# motor_driver_v3_0.net
KiCad netlist of a schematic drawn in EAGLE
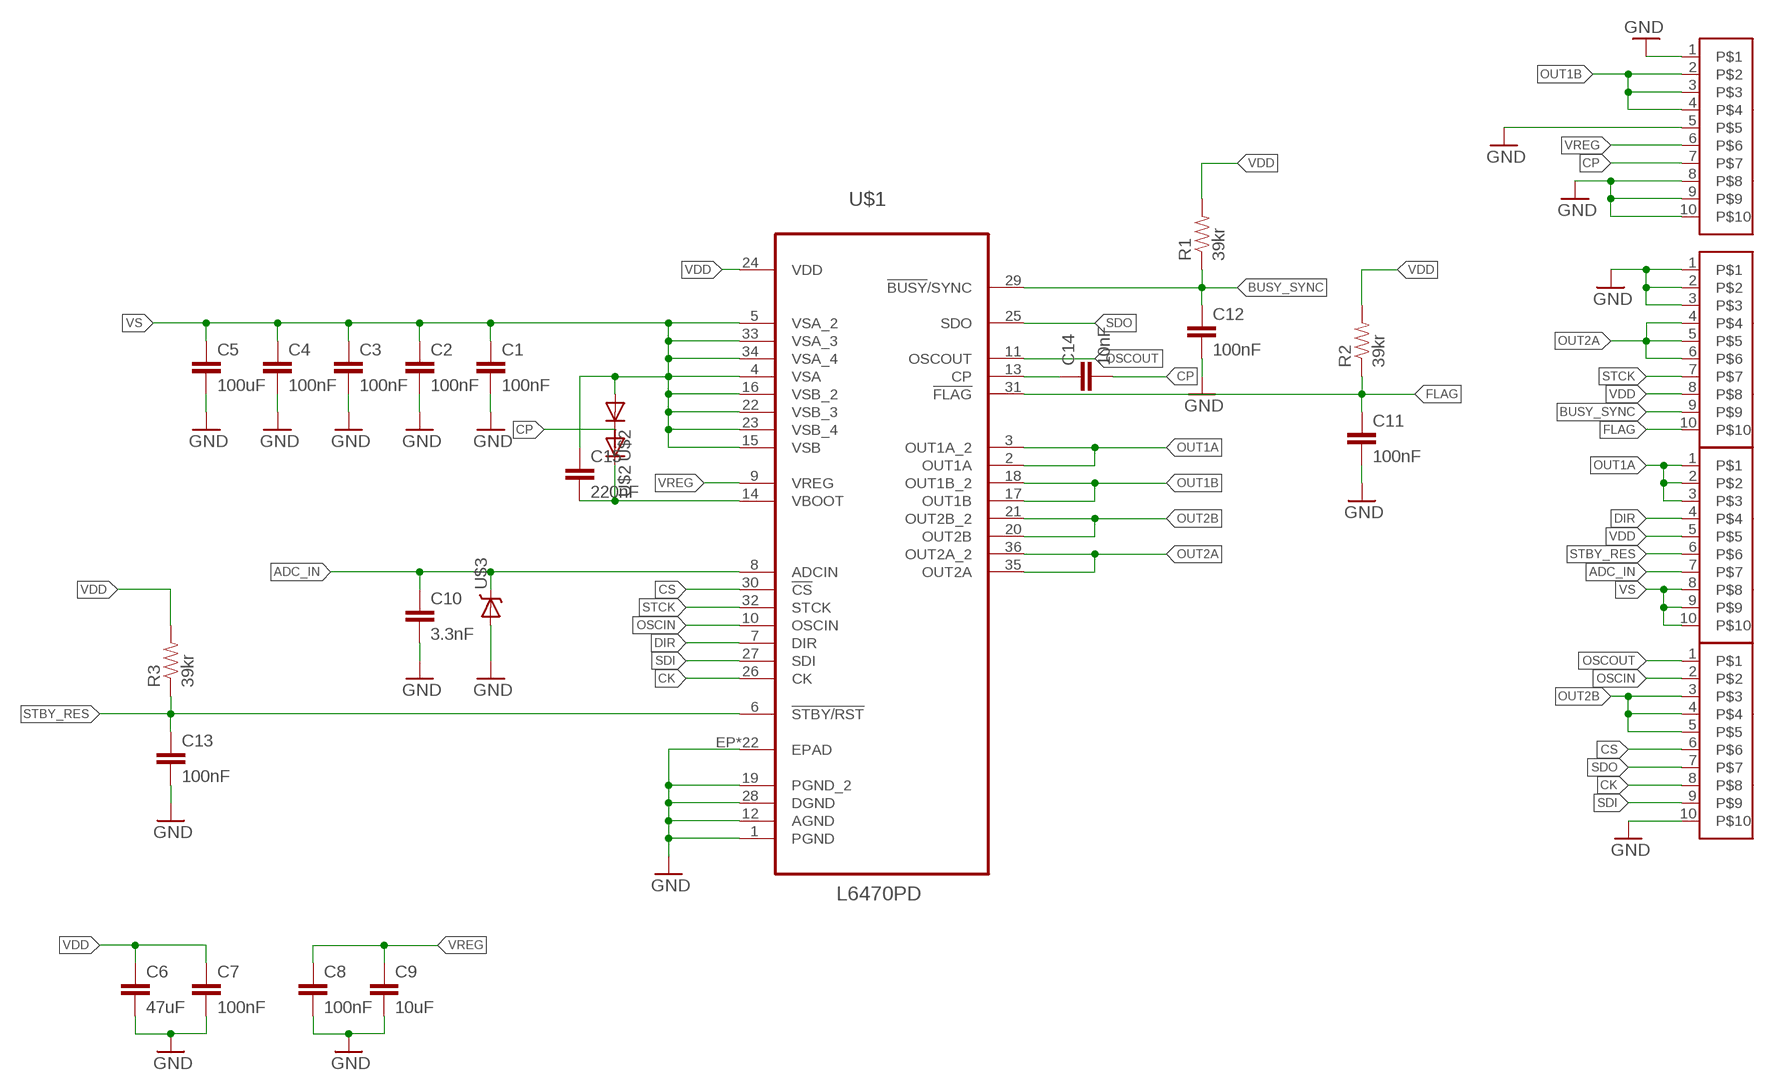
[diagram p0: schematic, sheet 1]

(export (version "E")
  (design (tool "Eeschema 10.0.6"))
  (components
    (comp (ref "C1")
      (value "100nF")
      (footprint "eagle-import:0805-CAP")
      (libsource (lib "eagle-import") (part "CAP0805"))
    )
    (comp (ref "C2")
      (value "100nF")
      (footprint "eagle-import:0805-CAP")
      (libsource (lib "eagle-import") (part "CAP0805"))
    )
    (comp (ref "C3")
      (value "100nF")
      (footprint "eagle-import:0805-CAP")
      (libsource (lib "eagle-import") (part "CAP0805"))
    )
    (comp (ref "C4")
      (value "100nF")
      (footprint "eagle-import:0805-CAP")
      (libsource (lib "eagle-import") (part "CAP0805"))
    )
    (comp (ref "C5")
      (value "100uF")
      (footprint "eagle-import:CAP-10X12")
      (libsource (lib "eagle-import") (part "CAP"))
    )
    (comp (ref "C6")
      (value "47uF")
      (footprint "eagle-import:1206-CAP")
      (libsource (lib "eagle-import") (part "CAP1206"))
    )
    (comp (ref "C7")
      (value "100nF")
      (footprint "eagle-import:0805-CAP")
      (libsource (lib "eagle-import") (part "CAP0805"))
    )
    (comp (ref "C8")
      (value "100nF")
      (footprint "eagle-import:0805-CAP")
      (libsource (lib "eagle-import") (part "CAP0805"))
    )
    (comp (ref "C9")
      (value "10uF")
      (footprint "eagle-import:0805-CAP")
      (libsource (lib "eagle-import") (part "CAP0805"))
    )
    (comp (ref "C10")
      (value "3.3nF")
      (footprint "eagle-import:0805-CAP")
      (libsource (lib "eagle-import") (part "CAP0805"))
    )
    (comp (ref "C11")
      (value "100nF")
      (footprint "eagle-import:0805-CAP")
      (libsource (lib "eagle-import") (part "CAP0805"))
    )
    (comp (ref "C12")
      (value "100nF")
      (footprint "eagle-import:0805-CAP")
      (libsource (lib "eagle-import") (part "CAP0805"))
    )
    (comp (ref "C13")
      (value "100nF")
      (footprint "eagle-import:0805-CAP")
      (libsource (lib "eagle-import") (part "CAP0805"))
    )
    (comp (ref "C14")
      (value "10nF")
      (footprint "eagle-import:0805-CAP")
      (libsource (lib "eagle-import") (part "CAP0805"))
    )
    (comp (ref "C15")
      (value "220nF")
      (footprint "eagle-import:0805-CAP")
      (libsource (lib "eagle-import") (part "CAP0805"))
    )
    (comp (ref "R1")
      (value "39kr")
      (footprint "eagle-import:0805")
      (libsource (lib "eagle-import") (part "RESISTOR"))
    )
    (comp (ref "R2")
      (value "39kr")
      (footprint "eagle-import:0805")
      (libsource (lib "eagle-import") (part "RESISTOR"))
    )
    (comp (ref "R3")
      (value "39kr")
      (footprint "eagle-import:0805")
      (libsource (lib "eagle-import") (part "RESISTOR"))
    )
    (comp (ref "U$1")
      (value "L6470PD")
      (footprint "eagle-import:SOP65P1400X360-37N")
      (libsource (lib "eagle-import") (part "L6470PD"))
    )
    (comp (ref "U$2")
      (value "BAV99")
      (footprint "eagle-import:BAV99")
      (libsource (lib "eagle-import") (part "BAV99"))
    )
    (comp (ref "U$3")
      (value "BZX585")
      (footprint "eagle-import:BZX585")
      (libsource (lib "eagle-import") (part "BZX585"))
    )
    (comp (ref "U$4")
      (value "CON_TH_10PINS")
      (footprint "eagle-import:CON_TH_10POS")
      (libsource (lib "eagle-import") (part "CON_TH_10PINS"))
    )
    (comp (ref "U$5")
      (value "CON_TH_10PINS")
      (footprint "eagle-import:CON_TH_10POS")
      (libsource (lib "eagle-import") (part "CON_TH_10PINS"))
    )
    (comp (ref "U$6")
      (value "CON_TH_10PINS")
      (footprint "eagle-import:CON_TH_10POS")
      (libsource (lib "eagle-import") (part "CON_TH_10PINS"))
    )
    (comp (ref "U$7")
      (value "CON_TH_10PINS")
      (footprint "eagle-import:CON_TH_10POS")
      (libsource (lib "eagle-import") (part "CON_TH_10PINS"))
    )
  )
  (nets
    (net (code "1") (name "ADC_IN") (class "Default")
      (node (ref "C10") (pin "P$1") (pinfunction "1_P$1") (pintype "passive"))
      (node (ref "U$1") (pin "8") (pinfunction "ADCIN_8") (pintype "input"))
      (node (ref "U$3") (pin "P$1") (pinfunction "1_P$1") (pintype "passive"))
      (node (ref "U$4") (pin "7") (pinfunction "P$7_7") (pintype "bidirectional"))
    )
    (net (code "2") (name "BUSY_SYNC") (class "Default")
      (node (ref "C12") (pin "P$1") (pinfunction "1_P$1") (pintype "passive"))
      (node (ref "R1") (pin "1") (pinfunction "1_1") (pintype "passive"))
      (node (ref "U$1") (pin "29") (pinfunction "~{BUSY}/SYNC_29") (pintype "output"))
      (node (ref "U$5") (pin "9") (pinfunction "P$9_9") (pintype "bidirectional"))
    )
    (net (code "3") (name "CK") (class "Default")
      (node (ref "U$1") (pin "26") (pinfunction "CK_26") (pintype "input"))
      (node (ref "U$7") (pin "8") (pinfunction "P$8_8") (pintype "bidirectional"))
    )
    (net (code "4") (name "CP") (class "Default")
      (node (ref "C14") (pin "P$2") (pinfunction "2_P$2") (pintype "passive"))
      (node (ref "U$2") (pin "P$3") (pinfunction "3_P$3") (pintype "passive"))
      (node (ref "U$6") (pin "7") (pinfunction "P$7_7") (pintype "bidirectional"))
    )
    (net (code "5") (name "CS") (class "Default")
      (node (ref "U$1") (pin "30") (pinfunction "~{CS}_30") (pintype "input"))
      (node (ref "U$7") (pin "6") (pinfunction "P$6_6") (pintype "bidirectional"))
    )
    (net (code "6") (name "DIR") (class "Default")
      (node (ref "U$1") (pin "7") (pinfunction "DIR_7") (pintype "passive"))
      (node (ref "U$4") (pin "4") (pinfunction "P$4_4") (pintype "bidirectional"))
    )
    (net (code "7") (name "FLAG") (class "Default")
      (node (ref "C11") (pin "P$1") (pinfunction "1_P$1") (pintype "passive"))
      (node (ref "R2") (pin "1") (pinfunction "1_1") (pintype "passive"))
      (node (ref "U$1") (pin "31") (pinfunction "~{FLAG}_31") (pintype "output"))
      (node (ref "U$5") (pin "10") (pinfunction "P$10_10") (pintype "bidirectional"))
    )
    (net (code "8") (name "GND") (class "Default")
      (node (ref "C1") (pin "P$2") (pinfunction "2_P$2") (pintype "passive"))
      (node (ref "C10") (pin "P$2") (pinfunction "2_P$2") (pintype "passive"))
      (node (ref "C11") (pin "P$2") (pinfunction "2_P$2") (pintype "passive"))
      (node (ref "C12") (pin "P$2") (pinfunction "2_P$2") (pintype "passive"))
      (node (ref "C13") (pin "P$2") (pinfunction "2_P$2") (pintype "passive"))
      (node (ref "C2") (pin "P$2") (pinfunction "2_P$2") (pintype "passive"))
      (node (ref "C3") (pin "P$2") (pinfunction "2_P$2") (pintype "passive"))
      (node (ref "C4") (pin "P$2") (pinfunction "2_P$2") (pintype "passive"))
      (node (ref "C5") (pin "P$2") (pinfunction "2_P$2") (pintype "passive"))
      (node (ref "C6") (pin "P$2") (pinfunction "2_P$2") (pintype "passive"))
      (node (ref "C7") (pin "P$2") (pinfunction "2_P$2") (pintype "passive"))
      (node (ref "C8") (pin "P$2") (pinfunction "2_P$2") (pintype "passive"))
      (node (ref "C9") (pin "P$2") (pinfunction "2_P$2") (pintype "passive"))
      (node (ref "U$1") (pin "1") (pinfunction "PGND_1") (pintype "passive"))
      (node (ref "U$1") (pin "12") (pinfunction "AGND_12") (pintype "passive"))
      (node (ref "U$1") (pin "19") (pinfunction "PGND_2_19") (pintype "passive"))
      (node (ref "U$1") (pin "28") (pinfunction "DGND_28") (pintype "passive"))
      (node (ref "U$1") (pin "EP") (pinfunction "EPAD_EP") (pintype "passive"))
      (node (ref "U$1") (pin "VIA1") (pinfunction "EPAD_VIA1") (pintype "passive"))
      (node (ref "U$1") (pin "VIA10") (pinfunction "EPAD_VIA10") (pintype "passive"))
      (node (ref "U$1") (pin "VIA11") (pinfunction "EPAD_VIA11") (pintype "passive"))
      (node (ref "U$1") (pin "VIA12") (pinfunction "EPAD_VIA12") (pintype "passive"))
      (node (ref "U$1") (pin "VIA13") (pinfunction "EPAD_VIA13") (pintype "passive"))
      (node (ref "U$1") (pin "VIA14") (pinfunction "EPAD_VIA14") (pintype "passive"))
      (node (ref "U$1") (pin "VIA15") (pinfunction "EPAD_VIA15") (pintype "passive"))
      (node (ref "U$1") (pin "VIA16") (pinfunction "EPAD_VIA16") (pintype "passive"))
      (node (ref "U$1") (pin "VIA17") (pinfunction "EPAD_VIA17") (pintype "passive"))
      (node (ref "U$1") (pin "VIA18") (pinfunction "EPAD_VIA18") (pintype "passive"))
      (node (ref "U$1") (pin "VIA19") (pinfunction "EPAD_VIA19") (pintype "passive"))
      (node (ref "U$1") (pin "VIA2") (pinfunction "EPAD_VIA2") (pintype "passive"))
      (node (ref "U$1") (pin "VIA20") (pinfunction "EPAD_VIA20") (pintype "passive"))
      (node (ref "U$1") (pin "VIA21") (pinfunction "EPAD_VIA21") (pintype "passive"))
      (node (ref "U$1") (pin "VIA3") (pinfunction "EPAD_VIA3") (pintype "passive"))
      (node (ref "U$1") (pin "VIA4") (pinfunction "EPAD_VIA4") (pintype "passive"))
      (node (ref "U$1") (pin "VIA5") (pinfunction "EPAD_VIA5") (pintype "passive"))
      (node (ref "U$1") (pin "VIA6") (pinfunction "EPAD_VIA6") (pintype "passive"))
      (node (ref "U$1") (pin "VIA7") (pinfunction "EPAD_VIA7") (pintype "passive"))
      (node (ref "U$1") (pin "VIA8") (pinfunction "EPAD_VIA8") (pintype "passive"))
      (node (ref "U$1") (pin "VIA9") (pinfunction "EPAD_VIA9") (pintype "passive"))
      (node (ref "U$3") (pin "P$2") (pinfunction "2_P$2") (pintype "passive"))
      (node (ref "U$5") (pin "1") (pinfunction "P$1_1") (pintype "bidirectional"))
      (node (ref "U$5") (pin "2") (pinfunction "P$2_2") (pintype "bidirectional"))
      (node (ref "U$5") (pin "3") (pinfunction "P$3_3") (pintype "bidirectional"))
      (node (ref "U$6") (pin "1") (pinfunction "P$1_1") (pintype "bidirectional"))
      (node (ref "U$6") (pin "10") (pinfunction "P$10_10") (pintype "bidirectional"))
      (node (ref "U$6") (pin "5") (pinfunction "P$5_5") (pintype "bidirectional"))
      (node (ref "U$6") (pin "8") (pinfunction "P$8_8") (pintype "bidirectional"))
      (node (ref "U$6") (pin "9") (pinfunction "P$9_9") (pintype "bidirectional"))
      (node (ref "U$7") (pin "10") (pinfunction "P$10_10") (pintype "bidirectional"))
    )
    (net (code "9") (name "Net-(C14-1)") (class "Default")
      (node (ref "C14") (pin "P$1") (pinfunction "1_P$1") (pintype "passive"))
      (node (ref "U$1") (pin "13") (pinfunction "CP_13") (pintype "output"))
    )
    (net (code "10") (name "Net-(C15-2)") (class "Default")
      (node (ref "C15") (pin "P$2") (pinfunction "2_P$2") (pintype "passive"))
      (node (ref "U$1") (pin "14") (pinfunction "VBOOT_14") (pintype "power_in"))
      (node (ref "U$2") (pin "P$2") (pinfunction "2_P$2") (pintype "passive"))
    )
    (net (code "11") (name "OSCIN") (class "Default")
      (node (ref "U$1") (pin "10") (pinfunction "OSCIN_10") (pintype "input"))
      (node (ref "U$7") (pin "2") (pinfunction "P$2_2") (pintype "bidirectional"))
    )
    (net (code "12") (name "OSCOUT") (class "Default")
      (node (ref "U$1") (pin "11") (pinfunction "OSCOUT_11") (pintype "output"))
      (node (ref "U$7") (pin "1") (pinfunction "P$1_1") (pintype "bidirectional"))
    )
    (net (code "13") (name "OUT1A") (class "Default")
      (node (ref "U$1") (pin "2") (pinfunction "OUT1A_2") (pintype "output"))
      (node (ref "U$1") (pin "3") (pinfunction "OUT1A_2_3") (pintype "output"))
      (node (ref "U$4") (pin "1") (pinfunction "P$1_1") (pintype "bidirectional"))
      (node (ref "U$4") (pin "2") (pinfunction "P$2_2") (pintype "bidirectional"))
      (node (ref "U$4") (pin "3") (pinfunction "P$3_3") (pintype "bidirectional"))
    )
    (net (code "14") (name "OUT1B") (class "Default")
      (node (ref "U$1") (pin "17") (pinfunction "OUT1B_17") (pintype "output"))
      (node (ref "U$1") (pin "18") (pinfunction "OUT1B_2_18") (pintype "output"))
      (node (ref "U$6") (pin "2") (pinfunction "P$2_2") (pintype "bidirectional"))
      (node (ref "U$6") (pin "3") (pinfunction "P$3_3") (pintype "bidirectional"))
      (node (ref "U$6") (pin "4") (pinfunction "P$4_4") (pintype "bidirectional"))
    )
    (net (code "15") (name "OUT2A") (class "Default")
      (node (ref "U$1") (pin "35") (pinfunction "OUT2A_35") (pintype "output"))
      (node (ref "U$1") (pin "36") (pinfunction "OUT2A_2_36") (pintype "output"))
      (node (ref "U$5") (pin "4") (pinfunction "P$4_4") (pintype "bidirectional"))
      (node (ref "U$5") (pin "5") (pinfunction "P$5_5") (pintype "bidirectional"))
      (node (ref "U$5") (pin "6") (pinfunction "P$6_6") (pintype "bidirectional"))
    )
    (net (code "16") (name "OUT2B") (class "Default")
      (node (ref "U$1") (pin "20") (pinfunction "OUT2B_20") (pintype "output"))
      (node (ref "U$1") (pin "21") (pinfunction "OUT2B_2_21") (pintype "output"))
      (node (ref "U$7") (pin "3") (pinfunction "P$3_3") (pintype "bidirectional"))
      (node (ref "U$7") (pin "4") (pinfunction "P$4_4") (pintype "bidirectional"))
      (node (ref "U$7") (pin "5") (pinfunction "P$5_5") (pintype "bidirectional"))
    )
    (net (code "17") (name "SDI") (class "Default")
      (node (ref "U$1") (pin "27") (pinfunction "SDI_27") (pintype "input"))
      (node (ref "U$7") (pin "9") (pinfunction "P$9_9") (pintype "bidirectional"))
    )
    (net (code "18") (name "SDO") (class "Default")
      (node (ref "U$1") (pin "25") (pinfunction "SDO_25") (pintype "output"))
      (node (ref "U$7") (pin "7") (pinfunction "P$7_7") (pintype "bidirectional"))
    )
    (net (code "19") (name "STBY_RES") (class "Default")
      (node (ref "C13") (pin "P$1") (pinfunction "1_P$1") (pintype "passive"))
      (node (ref "R3") (pin "1") (pinfunction "1_1") (pintype "passive"))
      (node (ref "U$1") (pin "6") (pinfunction "~{STBY/RST}_6") (pintype "input"))
      (node (ref "U$4") (pin "6") (pinfunction "P$6_6") (pintype "bidirectional"))
    )
    (net (code "20") (name "STCK") (class "Default")
      (node (ref "U$1") (pin "32") (pinfunction "STCK_32") (pintype "input"))
      (node (ref "U$5") (pin "7") (pinfunction "P$7_7") (pintype "bidirectional"))
    )
    (net (code "21") (name "VDD") (class "Default")
      (node (ref "C6") (pin "P$1") (pinfunction "1_P$1") (pintype "passive"))
      (node (ref "C7") (pin "P$1") (pinfunction "1_P$1") (pintype "passive"))
      (node (ref "R1") (pin "2") (pinfunction "2_2") (pintype "passive"))
      (node (ref "R2") (pin "2") (pinfunction "2_2") (pintype "passive"))
      (node (ref "R3") (pin "2") (pinfunction "2_2") (pintype "passive"))
      (node (ref "U$1") (pin "24") (pinfunction "VDD_24") (pintype "power_in"))
      (node (ref "U$4") (pin "5") (pinfunction "P$5_5") (pintype "bidirectional"))
      (node (ref "U$5") (pin "8") (pinfunction "P$8_8") (pintype "bidirectional"))
    )
    (net (code "22") (name "VREG") (class "Default")
      (node (ref "C8") (pin "P$1") (pinfunction "1_P$1") (pintype "passive"))
      (node (ref "C9") (pin "P$1") (pinfunction "1_P$1") (pintype "passive"))
      (node (ref "U$1") (pin "9") (pinfunction "VREG_9") (pintype "power_in"))
      (node (ref "U$6") (pin "6") (pinfunction "P$6_6") (pintype "bidirectional"))
    )
    (net (code "23") (name "VS") (class "Default")
      (node (ref "C1") (pin "P$1") (pinfunction "1_P$1") (pintype "passive"))
      (node (ref "C15") (pin "P$1") (pinfunction "1_P$1") (pintype "passive"))
      (node (ref "C2") (pin "P$1") (pinfunction "1_P$1") (pintype "passive"))
      (node (ref "C3") (pin "P$1") (pinfunction "1_P$1") (pintype "passive"))
      (node (ref "C4") (pin "P$1") (pinfunction "1_P$1") (pintype "passive"))
      (node (ref "C5") (pin "P$1") (pinfunction "1_P$1") (pintype "passive"))
      (node (ref "U$1") (pin "15") (pinfunction "VSB_15") (pintype "power_in"))
      (node (ref "U$1") (pin "16") (pinfunction "VSB_2_16") (pintype "power_in"))
      (node (ref "U$1") (pin "22") (pinfunction "VSB_3_22") (pintype "power_in"))
      (node (ref "U$1") (pin "23") (pinfunction "VSB_4_23") (pintype "power_in"))
      (node (ref "U$1") (pin "33") (pinfunction "VSA_3_33") (pintype "power_in"))
      (node (ref "U$1") (pin "34") (pinfunction "VSA_4_34") (pintype "power_in"))
      (node (ref "U$1") (pin "4") (pinfunction "VSA_4") (pintype "power_in"))
      (node (ref "U$1") (pin "5") (pinfunction "VSA_2_5") (pintype "power_in"))
      (node (ref "U$2") (pin "P$1") (pinfunction "1_P$1") (pintype "passive"))
      (node (ref "U$4") (pin "10") (pinfunction "P$10_10") (pintype "bidirectional"))
      (node (ref "U$4") (pin "8") (pinfunction "P$8_8") (pintype "bidirectional"))
      (node (ref "U$4") (pin "9") (pinfunction "P$9_9") (pintype "bidirectional"))
    )
  )
)
